# BatteryCharger.net
KiCad netlist of a schematic drawn in Altium Designer
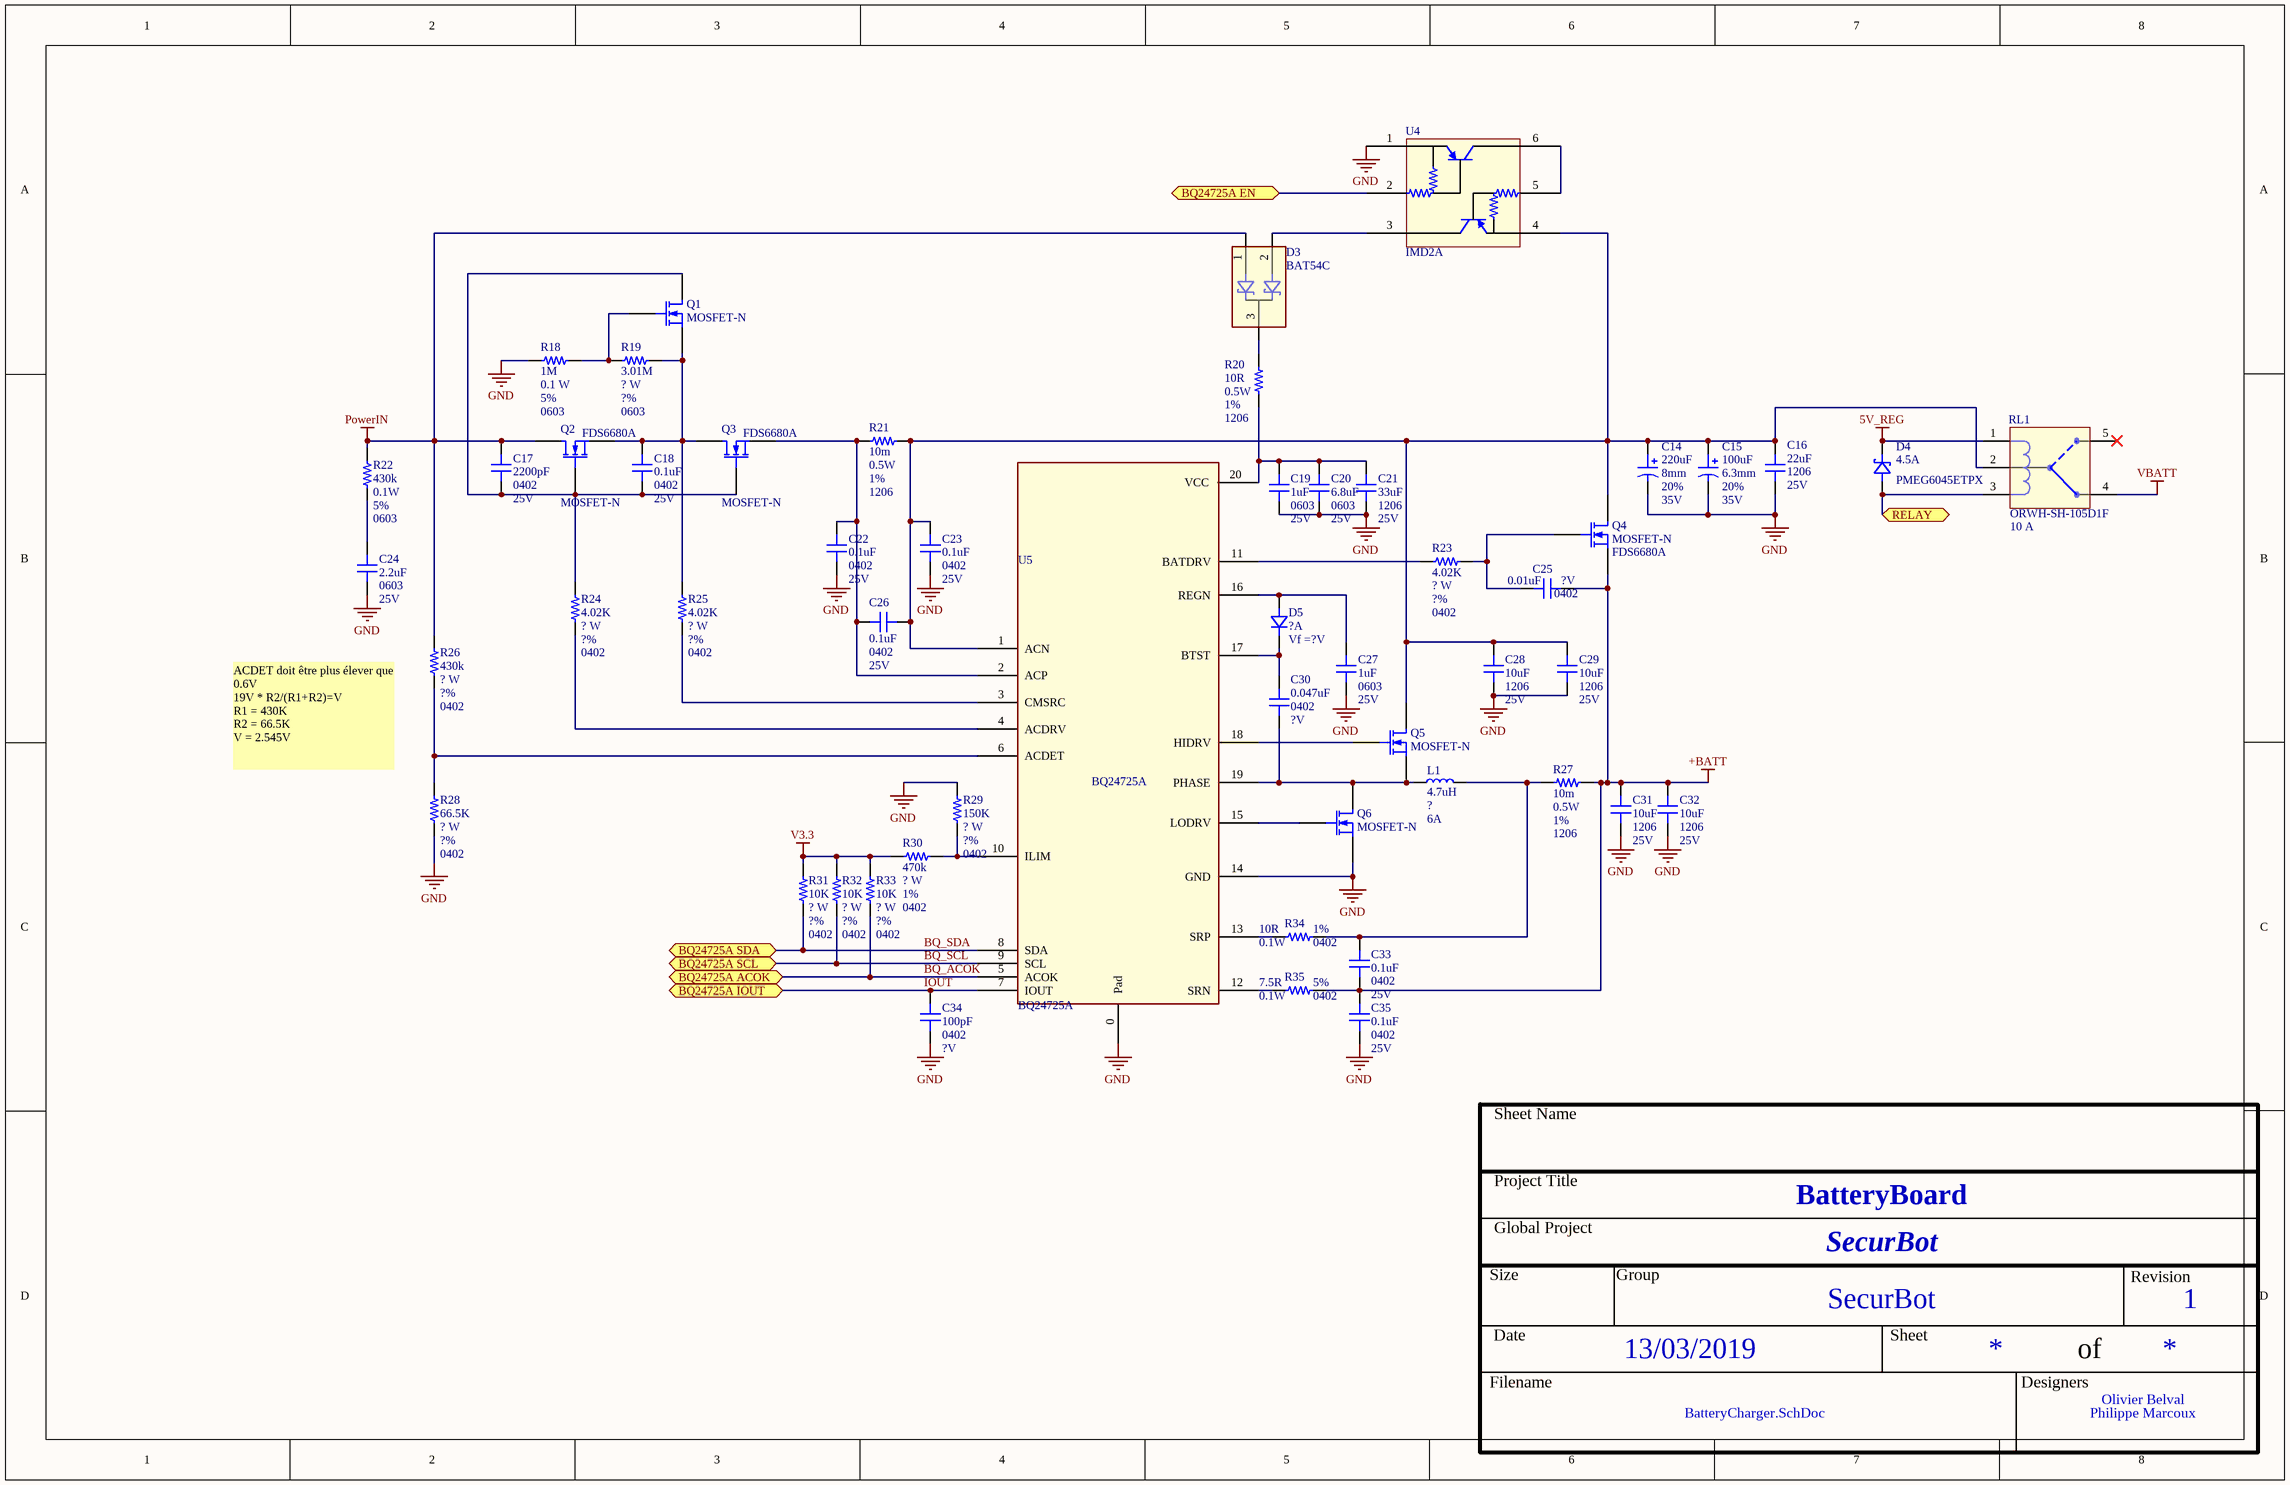
[diagram p0: BatteryCharger.SchDoc]

(export (version "E")
  (design (tool "Eeschema 10.0.6"))
  (components
    (comp (ref "C14")
      (value "220uF")
      (footprint "CAP UWT 8x10")
      (description "CAP ALU - 6.3mm")
      (fields
        (field (name "PACKAGE") "8mm")
        (field (name "TOLERANCE") "20%")
        (field (name "VOLTAGE") "35V")
        (field (name "PART NUMBER") "UWT1E221MNL1GS")
      )
      (libsource (lib "SecureBot") (part "CAP ALU - 6_3mm"))
    )
    (comp (ref "C15")
      (value "100uF")
      (footprint "CAP ALU - 6.3mm DIA")
      (description "CAP ALU - 6.3mm")
      (fields
        (field (name "PACKAGE") "6.3mm")
        (field (name "TOLERANCE") "20%")
        (field (name "VOLTAGE") "35V")
        (field (name "PART NUMBER") "UWT1E101MCL1GS")
      )
      (libsource (lib "SecureBot") (part "CAP ALU - 6_3mm"))
    )
    (comp (ref "C16")
      (value "22uF")
      (footprint "CAP_1206")
      (description "CAP - 1206")
      (fields
        (field (name "PART NUMBER") "CL31A226KAHNNNE")
        (field (name "PACKAGE") "1206")
        (field (name "VOLTAGE") "25V")
      )
      (libsource (lib "SecureBot") (part "CAP - 1206"))
    )
    (comp (ref "C17")
      (value "2200pF")
      (footprint "CAP_0402")
      (description "CAP - 0402")
      (fields
        (field (name "PART NUMBER") "AC0402KRX7R8BB222")
        (field (name "PACKAGE") "0402")
        (field (name "VOLTAGE") "25V")
      )
      (libsource (lib "SecureBot") (part "CAP - 0402"))
    )
    (comp (ref "C18")
      (value "0.1uF")
      (footprint "CAP_0402")
      (description "CAP - 0402")
      (fields
        (field (name "PART NUMBER") "CL05A104KA5NNNC")
        (field (name "PACKAGE") "0402")
        (field (name "VOLTAGE") "25V")
      )
      (libsource (lib "SecureBot") (part "CAP - 0402"))
    )
    (comp (ref "C19")
      (value "1uF")
      (footprint "CAP_0603")
      (description "CAP - 0603")
      (fields
        (field (name "PART NUMBER") "CL10A105KA8NNNC")
        (field (name "PACKAGE") "0603")
        (field (name "VOLTAGE") "25V")
      )
      (libsource (lib "SecureBot") (part "CAP - 0603"))
    )
    (comp (ref "C20")
      (value "6.8uF")
      (footprint "CAP_0603")
      (description "CAP - 0603")
      (fields
        (field (name "PART NUMBER") "C1608X5R1E685K080AC")
        (field (name "PACKAGE") "0603")
        (field (name "VOLTAGE") "25V")
      )
      (libsource (lib "SecureBot") (part "CAP - 0603"))
    )
    (comp (ref "C21")
      (value "33uF")
      (footprint "CAP_1206")
      (description "CAP - 1206")
      (fields
        (field (name "PART NUMBER") "C3216JB1E336M160AC")
        (field (name "PACKAGE") "1206")
        (field (name "VOLTAGE") "25V")
      )
      (libsource (lib "SecureBot") (part "CAP - 1206"))
    )
    (comp (ref "C22")
      (value "0.1uF")
      (footprint "CAP_0402")
      (description "CAP - 0402")
      (fields
        (field (name "PART NUMBER") "CL05A104KA5NNNC")
        (field (name "PACKAGE") "0402")
        (field (name "VOLTAGE") "25V")
      )
      (libsource (lib "SecureBot") (part "CAP - 0402"))
    )
    (comp (ref "C23")
      (value "0.1uF")
      (footprint "CAP_0402")
      (description "CAP - 0402")
      (fields
        (field (name "PART NUMBER") "CL05A104KA5NNNC")
        (field (name "PACKAGE") "0402")
        (field (name "VOLTAGE") "25V")
      )
      (libsource (lib "SecureBot") (part "CAP - 0402"))
    )
    (comp (ref "C24")
      (value "2.2uF")
      (footprint "CAP_0603")
      (description "CAP - 0603")
      (fields
        (field (name "PART NUMBER") "GRM188R61E225KA12D")
        (field (name "PACKAGE") "0603")
        (field (name "VOLTAGE") "25V")
      )
      (libsource (lib "SecureBot") (part "CAP - 0603"))
    )
    (comp (ref "C25")
      (value "0.01uF")
      (footprint "CAP_0402")
      (description "CAP - 0402")
      (fields
        (field (name "PART NUMBER") "CL05B103KA5NNNC")
        (field (name "PACKAGE") "0402")
        (field (name "VOLTAGE") "?V")
      )
      (libsource (lib "SecureBot") (part "CAP - 0402"))
    )
    (comp (ref "C26")
      (value "0.1uF")
      (footprint "CAP_0402")
      (description "CAP - 0402")
      (fields
        (field (name "PART NUMBER") "CL05A104KA5NNNC")
        (field (name "PACKAGE") "0402")
        (field (name "VOLTAGE") "25V")
      )
      (libsource (lib "SecureBot") (part "CAP - 0402"))
    )
    (comp (ref "C27")
      (value "1uF")
      (footprint "CAP_0603")
      (description "CAP - 0603")
      (fields
        (field (name "PART NUMBER") "CL10A105KA8NNNC")
        (field (name "PACKAGE") "0603")
        (field (name "VOLTAGE") "25V")
      )
      (libsource (lib "SecureBot") (part "CAP - 0603"))
    )
    (comp (ref "C28")
      (value "10uF")
      (footprint "CAP_1206")
      (description "CAP - 1206")
      (fields
        (field (name "PART NUMBER") "CL31A106KAHNFNE")
        (field (name "PACKAGE") "1206")
        (field (name "VOLTAGE") "25V")
      )
      (libsource (lib "SecureBot") (part "CAP - 1206"))
    )
    (comp (ref "C29")
      (value "10uF")
      (footprint "CAP_1206")
      (description "CAP - 1206")
      (fields
        (field (name "PART NUMBER") "CL31A106KAHNFNE")
        (field (name "PACKAGE") "1206")
        (field (name "VOLTAGE") "25V")
      )
      (libsource (lib "SecureBot") (part "CAP - 1206"))
    )
    (comp (ref "C30")
      (value "0.047uF")
      (footprint "CAP_0402")
      (description "CAP - 0402")
      (fields
        (field (name "PART NUMBER") "C0402C473K3RACAUTO")
        (field (name "PACKAGE") "0402")
        (field (name "VOLTAGE") "?V")
      )
      (libsource (lib "SecureBot") (part "CAP - 0402"))
    )
    (comp (ref "C31")
      (value "10uF")
      (footprint "CAP_1206")
      (description "CAP - 1206")
      (fields
        (field (name "PART NUMBER") "CL31A106KAHNFNE")
        (field (name "PACKAGE") "1206")
        (field (name "VOLTAGE") "25V")
      )
      (libsource (lib "SecureBot") (part "CAP - 1206"))
    )
    (comp (ref "C32")
      (value "10uF")
      (footprint "CAP_1206")
      (description "CAP - 1206")
      (fields
        (field (name "PART NUMBER") "CL31A106KAHNFNE")
        (field (name "PACKAGE") "1206")
        (field (name "VOLTAGE") "25V")
      )
      (libsource (lib "SecureBot") (part "CAP - 1206"))
    )
    (comp (ref "C33")
      (value "0.1uF")
      (footprint "CAP_0402")
      (description "CAP - 0402")
      (fields
        (field (name "PART NUMBER") "CL05A104KA5NNNC")
        (field (name "PACKAGE") "0402")
        (field (name "VOLTAGE") "25V")
      )
      (libsource (lib "SecureBot") (part "CAP - 0402"))
    )
    (comp (ref "C34")
      (value "100pF")
      (footprint "CAP_0402")
      (description "CAP - 0402")
      (fields
        (field (name "PART NUMBER") "CC0402KRX7R8BB101")
        (field (name "PACKAGE") "0402")
        (field (name "VOLTAGE") "?V")
      )
      (libsource (lib "SecureBot") (part "CAP - 0402"))
    )
    (comp (ref "C35")
      (value "0.1uF")
      (footprint "CAP_0402")
      (description "CAP - 0402")
      (fields
        (field (name "PART NUMBER") "CL05A104KA5NNNC")
        (field (name "PACKAGE") "0402")
        (field (name "VOLTAGE") "25V")
      )
      (libsource (lib "SecureBot") (part "CAP - 0402"))
    )
    (comp (ref "D3") (value "BAT54C") (footprint "BAT54C") (libsource (lib "SecureBot") (part "BAT54C")))
    (comp (ref "D4")
      (value "SCHOTTKEY")
      (footprint "DO-214AC_SOD128")
      (fields (field (name "CURRENT") "4.5A") (field (name "PART NUMBER") "PMEG6045ETPX"))
      (libsource (lib "SecureBot") (part "SCHOTTKEY"))
    )
    (comp (ref "D5")
      (value "DIODE BAT54")
      (footprint "BAT54")
      (fields
        (field (name "CURRENT") "?A")
        (field (name "VF") "Vf =?V")
        (field (name "PART NUMBER") "BAT54C")
      )
      (libsource (lib "SecureBot") (part "DIODE BAT54"))
    )
    (comp (ref "L1")
      (value "4.7uH")
      (footprint "ASPI-0630LR")
      (description "IND")
      (fields
        (field (name "PACKAGE") "?")
        (field (name "CURRENT") "6A")
        (field (name "PART NUMBER") "ASPI-0630LR-4R7M-T15")
      )
      (libsource (lib "SecureBot") (part "IND"))
    )
    (comp (ref "Q1")
      (value "MOSFET-N")
      (footprint "PG-SOT-323")
      (description "N-Channel MOSFET")
      (fields (field (name "PART NUMBER") "BSS138WH6327XTSA1") (field (name "PUBLISHER") "Altium Limited"))
      (libsource (lib "Miscellaneous Devices") (part "MOSFET-N"))
    )
    (comp (ref "Q2")
      (value "MOSFET-N")
      (footprint "SO-8 FDS6680AS")
      (description "N-Channel MOSFET")
      (fields (field (name "PART NUMBER") "FDS6680A") (field (name "PUBLISHER") "Altium Limited"))
      (libsource (lib "") (part "MOSFET-N_1"))
    )
    (comp (ref "Q3")
      (value "MOSFET-N")
      (footprint "SO-8 FDS6680AS")
      (description "N-Channel MOSFET")
      (fields (field (name "PART NUMBER") "FDS6680A") (field (name "PUBLISHER") "Altium Limited"))
      (libsource (lib "") (part "MOSFET-N_1"))
    )
    (comp (ref "Q4")
      (value "MOSFET-N")
      (footprint "SO-8 FDS6680AS")
      (description "N-Channel MOSFET")
      (fields (field (name "PART NUMBER") "FDS6680A") (field (name "PUBLISHER") "Altium Limited"))
      (libsource (lib "") (part "MOSFET-N_1"))
    )
    (comp (ref "Q5")
      (value "MOSFET-N")
      (footprint "SiS412DN")
      (description "N-Channel MOSFET")
      (fields (field (name "PART NUMBER") "SIS412DN-T1-GE3") (field (name "PUBLISHER") "Altium Limited"))
      (libsource (lib "") (part "MOSFET-N_1"))
    )
    (comp (ref "Q6")
      (value "MOSFET-N")
      (footprint "SiS412DN")
      (description "N-Channel MOSFET")
      (fields (field (name "PART NUMBER") "SIS412DN-T1-GE3") (field (name "PUBLISHER") "Altium Limited"))
      (libsource (lib "") (part "MOSFET-N_1"))
    )
    (comp (ref "R18")
      (value "1M")
      (footprint "RES_0603")
      (description "RES - 0603")
      (fields
        (field (name "PART NUMBER") "CRGCQ0603J1M0")
        (field (name "WATT") "0.1 W")
        (field (name "TOLERANCE") "5%")
        (field (name "PACKAGE") "0603")
      )
      (libsource (lib "SecureBot") (part "RES - 0603"))
    )
    (comp (ref "R19")
      (value "3.01M")
      (footprint "RES_0603")
      (description "RES - 0603")
      (fields
        (field (name "PART NUMBER") "RC0603FR-073M01L")
        (field (name "WATT") "? W")
        (field (name "TOLERANCE") "?%")
        (field (name "PACKAGE") "0603")
      )
      (libsource (lib "SecureBot") (part "RES - 0603"))
    )
    (comp (ref "R20")
      (value "10R")
      (footprint "RES_1206")
      (description "RES - 1206")
      (fields
        (field (name "PART NUMBER") "CRM1206-FX-10R0ELF")
        (field (name "WATT") "0.5W")
        (field (name "TOLERANCE") "1%")
        (field (name "PACKAGE") "1206")
      )
      (libsource (lib "SecureBot") (part "RES - 1206"))
    )
    (comp (ref "R21")
      (value "10m")
      (footprint "RES_1206")
      (description "RES - 1206")
      (fields
        (field (name "PART NUMBER") "KRL1632E-M-R010-F-T5")
        (field (name "WATT") "0.5W")
        (field (name "TOLERANCE") "1%")
        (field (name "PACKAGE") "1206")
      )
      (libsource (lib "SecureBot") (part "RES - 1206"))
    )
    (comp (ref "R22")
      (value "430k")
      (footprint "RES_0603")
      (description "RES - 0603")
      (fields
        (field (name "PART NUMBER") "RC0603JR-07430KL")
        (field (name "WATT") "0.1W")
        (field (name "TOLERANCE") "5%")
        (field (name "PACKAGE") "0603")
      )
      (libsource (lib "SecureBot") (part "RES - 0603"))
    )
    (comp (ref "R23")
      (value "4.02K")
      (footprint "RES_0402")
      (description "RES - 0402")
      (fields
        (field (name "PART NUMBER") "ERJ-2RKF4021X")
        (field (name "WATT") "? W")
        (field (name "TOLERANCE") "?%")
        (field (name "PACKAGE") "0402")
      )
      (libsource (lib "SecureBot") (part "RES - 0402"))
    )
    (comp (ref "R24")
      (value "4.02K")
      (footprint "RES_0402")
      (description "RES - 0402")
      (fields
        (field (name "PART NUMBER") "ERJ-2RKF4021X")
        (field (name "WATT") "? W")
        (field (name "TOLERANCE") "?%")
        (field (name "PACKAGE") "0402")
      )
      (libsource (lib "SecureBot") (part "RES - 0402"))
    )
    (comp (ref "R25")
      (value "4.02K")
      (footprint "RES_0402")
      (description "RES - 0402")
      (fields
        (field (name "PART NUMBER") "ERJ-2RKF4021X")
        (field (name "WATT") "? W")
        (field (name "TOLERANCE") "?%")
        (field (name "PACKAGE") "0402")
      )
      (libsource (lib "SecureBot") (part "RES - 0402"))
    )
    (comp (ref "R26")
      (value "430k")
      (footprint "RES_0402")
      (description "RES - 0402")
      (fields
        (field (name "PART NUMBER") "RC0402FR-07430KL")
        (field (name "WATT") "? W")
        (field (name "TOLERANCE") "?%")
        (field (name "PACKAGE") "0402")
      )
      (libsource (lib "SecureBot") (part "RES - 0402"))
    )
    (comp (ref "R27")
      (value "10m")
      (footprint "RES_1206")
      (description "RES - 1206")
      (fields
        (field (name "PART NUMBER") "KRL1632E-M-R010-F-T5")
        (field (name "WATT") "0.5W")
        (field (name "TOLERANCE") "1%")
        (field (name "PACKAGE") "1206")
      )
      (libsource (lib "SecureBot") (part "RES - 1206"))
    )
    (comp (ref "R28")
      (value "66.5K")
      (footprint "RES_0402")
      (description "RES - 0402")
      (fields
        (field (name "PART NUMBER") "RMCF0402FT66K5")
        (field (name "WATT") "? W")
        (field (name "TOLERANCE") "?%")
        (field (name "PACKAGE") "0402")
      )
      (libsource (lib "SecureBot") (part "RES - 0402"))
    )
    (comp (ref "R29")
      (value "150K")
      (footprint "RES_0402")
      (description "RES - 0402")
      (fields
        (field (name "PART NUMBER") "MCS04020C1503FE000")
        (field (name "WATT") "? W")
        (field (name "TOLERANCE") "?%")
        (field (name "PACKAGE") "0402")
      )
      (libsource (lib "SecureBot") (part "RES - 0402"))
    )
    (comp (ref "R30")
      (value "470k")
      (footprint "RES_0402")
      (description "RES - 0402")
      (fields
        (field (name "PART NUMBER") "MCS04020C4703FE000")
        (field (name "WATT") "? W")
        (field (name "TOLERANCE") "1%")
        (field (name "PACKAGE") "0402")
      )
      (libsource (lib "SecureBot") (part "RES - 0402"))
    )
    (comp (ref "R31")
      (value "10K")
      (footprint "RES_0402")
      (description "RES - 0402")
      (fields
        (field (name "PART NUMBER") "MCS0402MC1002FE000")
        (field (name "WATT") "? W")
        (field (name "TOLERANCE") "?%")
        (field (name "PACKAGE") "0402")
      )
      (libsource (lib "SecureBot") (part "RES - 0402"))
    )
    (comp (ref "R32")
      (value "10K")
      (footprint "RES_0402")
      (description "RES - 0402")
      (fields
        (field (name "PART NUMBER") "MCS0402MC1002FE000")
        (field (name "WATT") "? W")
        (field (name "TOLERANCE") "?%")
        (field (name "PACKAGE") "0402")
      )
      (libsource (lib "SecureBot") (part "RES - 0402"))
    )
    (comp (ref "R33")
      (value "10K")
      (footprint "RES_0402")
      (description "RES - 0402")
      (fields
        (field (name "PART NUMBER") "MCS0402MC1002FE000")
        (field (name "WATT") "? W")
        (field (name "TOLERANCE") "?%")
        (field (name "PACKAGE") "0402")
      )
      (libsource (lib "SecureBot") (part "RES - 0402"))
    )
    (comp (ref "R34")
      (value "10R")
      (footprint "RES_0402")
      (description "RES - 0402")
      (fields
        (field (name "PART NUMBER") "ERJ-2RKF10R0X")
        (field (name "WATT") "0.1W")
        (field (name "TOLERANCE") "1%")
        (field (name "PACKAGE") "0402")
      )
      (libsource (lib "SecureBot") (part "RES - 0402"))
    )
    (comp (ref "R35")
      (value "7.5R")
      (footprint "RES_0402")
      (description "RES - 0402")
      (fields
        (field (name "PART NUMBER") "ERJ-2GEJ7R5X")
        (field (name "WATT") "0.1W")
        (field (name "TOLERANCE") "5%")
        (field (name "PACKAGE") "0402")
      )
      (libsource (lib "SecureBot") (part "RES - 0402"))
    )
    (comp (ref "RL1")
      (value "Relay SPDT")
      (footprint "ORWH-SH")
      (fields (field (name "PART NUMBER") "ORWH-SH-105D1F") (field (name "A MAX") "10 A"))
      (libsource (lib "SecureBot") (part "Relay SPDT"))
    )
    (comp (ref "U4")
      (value "IMD2A")
      (footprint "IMD2A")
      (description "Dual digital Transistor")
      (libsource (lib "SecureBot") (part "IMD2A"))
    )
    (comp (ref "U5")
      (value "BQ24725A")
      (footprint "bq24725A")
      (libsource (lib "SecureBot") (part "BQ24725A"))
    )
  )
  (nets
    (net (code "1") (name "+BATT") (class "Default")
      (node (ref "C25") (pin "2") (pinfunction "2_2") (pintype "passive"))
      (node (ref "C31") (pin "1") (pinfunction "1_1") (pintype "passive"))
      (node (ref "C32") (pin "1") (pinfunction "1_1") (pintype "passive"))
      (node (ref "C33") (pin "1") (pinfunction "1_1") (pintype "passive"))
      (node (ref "C35") (pin "2") (pinfunction "2_2") (pintype "passive"))
      (node (ref "Q4") (pin "3") (pinfunction "S_3") (pintype "passive"))
      (node (ref "R27") (pin "2") (pinfunction "2_2") (pintype "passive"))
      (node (ref "R35") (pin "2") (pinfunction "2_2") (pintype "passive"))
    )
    (net (code "2") (name "/BQ24725A EN") (class "Default")
      (node (ref "U4") (pin "2") (pinfunction "2_2") (pintype "passive"))
    )
    (net (code "3") (name "/BQ_ACOK") (class "Default")
      (node (ref "R33") (pin "2") (pinfunction "2_2") (pintype "passive"))
      (node (ref "U5") (pin "5") (pinfunction "ACOK_5") (pintype "passive"))
    )
    (net (code "4") (name "/BQ_SCL") (class "Default")
      (node (ref "R32") (pin "2") (pinfunction "2_2") (pintype "passive"))
      (node (ref "U5") (pin "9") (pinfunction "SCL_9") (pintype "passive"))
    )
    (net (code "5") (name "/BQ_SDA") (class "Default")
      (node (ref "R31") (pin "2") (pinfunction "2_2") (pintype "passive"))
      (node (ref "U5") (pin "8") (pinfunction "SDA_8") (pintype "passive"))
    )
    (net (code "6") (name "/IOUT") (class "Default")
      (node (ref "C34") (pin "1") (pinfunction "1_1") (pintype "passive"))
      (node (ref "U5") (pin "7") (pinfunction "IOUT_7") (pintype "passive"))
    )
    (net (code "7") (name "/RELAY") (class "Default")
      (node (ref "D4") (pin "1") (pinfunction "1_1") (pintype "passive"))
      (node (ref "RL1") (pin "3") (pinfunction "3_3") (pintype "passive"))
    )
    (net (code "8") (name "5V_REG") (class "Default")
      (node (ref "D4") (pin "2") (pinfunction "2_2") (pintype "passive"))
      (node (ref "RL1") (pin "1") (pinfunction "1_1") (pintype "passive"))
    )
    (net (code "9") (name "GND") (class "Default")
      (node (ref "C14") (pin "2") (pinfunction "2_2") (pintype "passive"))
      (node (ref "C15") (pin "2") (pinfunction "2_2") (pintype "passive"))
      (node (ref "C16") (pin "2") (pinfunction "2_2") (pintype "passive"))
      (node (ref "C19") (pin "2") (pinfunction "2_2") (pintype "passive"))
      (node (ref "C20") (pin "2") (pinfunction "2_2") (pintype "passive"))
      (node (ref "C21") (pin "2") (pinfunction "2_2") (pintype "passive"))
      (node (ref "C22") (pin "1") (pinfunction "1_1") (pintype "passive"))
      (node (ref "C23") (pin "1") (pinfunction "1_1") (pintype "passive"))
      (node (ref "C24") (pin "2") (pinfunction "2_2") (pintype "passive"))
      (node (ref "C27") (pin "2") (pinfunction "2_2") (pintype "passive"))
      (node (ref "C28") (pin "2") (pinfunction "2_2") (pintype "passive"))
      (node (ref "C29") (pin "2") (pinfunction "2_2") (pintype "passive"))
      (node (ref "C31") (pin "2") (pinfunction "2_2") (pintype "passive"))
      (node (ref "C32") (pin "2") (pinfunction "2_2") (pintype "passive"))
      (node (ref "C34") (pin "2") (pinfunction "2_2") (pintype "passive"))
      (node (ref "C35") (pin "1") (pinfunction "1_1") (pintype "passive"))
      (node (ref "Q6") (pin "3") (pinfunction "S_3") (pintype "passive"))
      (node (ref "R18") (pin "1") (pinfunction "1_1") (pintype "passive"))
      (node (ref "R28") (pin "2") (pinfunction "2_2") (pintype "passive"))
      (node (ref "R29") (pin "2") (pinfunction "2_2") (pintype "passive"))
      (node (ref "U4") (pin "1") (pinfunction "1_1") (pintype "passive"))
      (node (ref "U5") (pin "0") (pinfunction "Pad_0") (pintype "passive"))
      (node (ref "U5") (pin "14") (pinfunction "GND_14") (pintype "passive"))
    )
    (net (code "10") (name "Net-(C24-Pad1)") (class "Default")
      (node (ref "C24") (pin "1") (pinfunction "1_1") (pintype "passive"))
      (node (ref "R22") (pin "2") (pinfunction "2_2") (pintype "passive"))
    )
    (net (code "11") (name "Net-(C33-Pad2)") (class "Default")
      (node (ref "C33") (pin "2") (pinfunction "2_2") (pintype "passive"))
      (node (ref "L1") (pin "2") (pinfunction "2_2") (pintype "passive"))
      (node (ref "R27") (pin "1") (pinfunction "1_1") (pintype "passive"))
      (node (ref "R34") (pin "2") (pinfunction "2_2") (pintype "passive"))
    )
    (net (code "12") (name "Net-(D3-Pad2)") (class "Default")
      (node (ref "D3") (pin "2") (pinfunction "2_2") (pintype "passive"))
      (node (ref "U4") (pin "3") (pinfunction "3_3") (pintype "passive"))
    )
    (net (code "13") (name "Net-(D3-Pad3)") (class "Default")
      (node (ref "D3") (pin "3") (pinfunction "3_3") (pintype "passive"))
      (node (ref "R20") (pin "2") (pinfunction "2_2") (pintype "passive"))
    )
    (net (code "14") (name "Net-(Q1-D)") (class "Default")
      (node (ref "C17") (pin "1") (pinfunction "1_1") (pintype "passive"))
      (node (ref "C18") (pin "1") (pinfunction "1_1") (pintype "passive"))
      (node (ref "Q1") (pin "3") (pinfunction "D_3") (pintype "passive"))
      (node (ref "Q2") (pin "2") (pinfunction "G_2") (pintype "passive"))
      (node (ref "Q3") (pin "2") (pinfunction "G_2") (pintype "passive"))
      (node (ref "R24") (pin "1") (pinfunction "1_1") (pintype "passive"))
    )
    (net (code "15") (name "Net-(Q1-G)") (class "Default")
      (node (ref "Q1") (pin "1") (pinfunction "G_1") (pintype "passive"))
      (node (ref "R18") (pin "2") (pinfunction "2_2") (pintype "passive"))
      (node (ref "R19") (pin "1") (pinfunction "1_1") (pintype "passive"))
    )
    (net (code "16") (name "Net-(Q1-S)") (class "Default")
      (node (ref "C18") (pin "2") (pinfunction "2_2") (pintype "passive"))
      (node (ref "Q1") (pin "2") (pinfunction "S_2") (pintype "passive"))
      (node (ref "Q2") (pin "3") (pinfunction "S_3") (pintype "passive"))
      (node (ref "Q3") (pin "1") (pinfunction "D_1") (pintype "passive"))
      (node (ref "R19") (pin "2") (pinfunction "2_2") (pintype "passive"))
      (node (ref "R25") (pin "1") (pinfunction "1_1") (pintype "passive"))
    )
    (net (code "17") (name "Net-(Q3-S)") (class "Default")
      (node (ref "C22") (pin "2") (pinfunction "2_2") (pintype "passive"))
      (node (ref "C26") (pin "2") (pinfunction "2_2") (pintype "passive"))
      (node (ref "Q3") (pin "3") (pinfunction "S_3") (pintype "passive"))
      (node (ref "R21") (pin "1") (pinfunction "1_1") (pintype "passive"))
      (node (ref "U5") (pin "2") (pinfunction "ACP_2") (pintype "passive"))
    )
    (net (code "18") (name "Net-(Q4-D)") (class "Default")
      (node (ref "C14") (pin "1") (pinfunction "1_1") (pintype "passive"))
      (node (ref "C15") (pin "1") (pinfunction "1_1") (pintype "passive"))
      (node (ref "C16") (pin "1") (pinfunction "1_1") (pintype "passive"))
      (node (ref "C23") (pin "2") (pinfunction "2_2") (pintype "passive"))
      (node (ref "C26") (pin "1") (pinfunction "1_1") (pintype "passive"))
      (node (ref "C28") (pin "1") (pinfunction "1_1") (pintype "passive"))
      (node (ref "C29") (pin "1") (pinfunction "1_1") (pintype "passive"))
      (node (ref "Q4") (pin "1") (pinfunction "D_1") (pintype "passive"))
      (node (ref "Q5") (pin "1") (pinfunction "D_1") (pintype "passive"))
      (node (ref "R21") (pin "2") (pinfunction "2_2") (pintype "passive"))
      (node (ref "RL1") (pin "2") (pinfunction "2_2") (pintype "passive"))
      (node (ref "U4") (pin "4") (pinfunction "4_4") (pintype "passive"))
      (node (ref "U5") (pin "1") (pinfunction "ACN_1") (pintype "passive"))
    )
    (net (code "19") (name "Net-(Q4-G)") (class "Default")
      (node (ref "C25") (pin "1") (pinfunction "1_1") (pintype "passive"))
      (node (ref "Q4") (pin "2") (pinfunction "G_2") (pintype "passive"))
      (node (ref "R23") (pin "2") (pinfunction "2_2") (pintype "passive"))
    )
    (net (code "20") (name "Net-(Q5-G)") (class "Default")
      (node (ref "Q5") (pin "2") (pinfunction "G_2") (pintype "passive"))
      (node (ref "U5") (pin "18") (pinfunction "HIDRV_18") (pintype "passive"))
    )
    (net (code "21") (name "Net-(Q5-S)") (class "Default")
      (node (ref "C30") (pin "2") (pinfunction "2_2") (pintype "passive"))
      (node (ref "L1") (pin "1") (pinfunction "1_1") (pintype "passive"))
      (node (ref "Q5") (pin "3") (pinfunction "S_3") (pintype "passive"))
      (node (ref "Q6") (pin "1") (pinfunction "D_1") (pintype "passive"))
      (node (ref "U5") (pin "19") (pinfunction "PHASE_19") (pintype "passive"))
    )
    (net (code "22") (name "Net-(Q6-G)") (class "Default")
      (node (ref "Q6") (pin "2") (pinfunction "G_2") (pintype "passive"))
      (node (ref "U5") (pin "15") (pinfunction "LODRV_15") (pintype "passive"))
    )
    (net (code "23") (name "Net-(U4-Pad5)") (class "Default")
      (node (ref "U4") (pin "5") (pinfunction "5_5") (pintype "passive"))
      (node (ref "U4") (pin "6") (pinfunction "6_6") (pintype "passive"))
    )
    (net (code "24") (name "Net-(U5-ACDET)") (class "Default")
      (node (ref "R26") (pin "2") (pinfunction "2_2") (pintype "passive"))
      (node (ref "R28") (pin "1") (pinfunction "1_1") (pintype "passive"))
      (node (ref "U5") (pin "6") (pinfunction "ACDET_6") (pintype "passive"))
    )
    (net (code "25") (name "Net-(U5-ACDRV)") (class "Default")
      (node (ref "R24") (pin "2") (pinfunction "2_2") (pintype "passive"))
      (node (ref "U5") (pin "4") (pinfunction "ACDRV_4") (pintype "passive"))
    )
    (net (code "26") (name "Net-(U5-BATDRV)") (class "Default")
      (node (ref "R23") (pin "1") (pinfunction "1_1") (pintype "passive"))
      (node (ref "U5") (pin "11") (pinfunction "BATDRV_11") (pintype "passive"))
    )
    (net (code "27") (name "Net-(U5-BTST)") (class "Default")
      (node (ref "C30") (pin "1") (pinfunction "1_1") (pintype "passive"))
      (node (ref "D5") (pin "3") (pinfunction "3_3") (pintype "passive"))
      (node (ref "U5") (pin "17") (pinfunction "BTST_17") (pintype "passive"))
    )
    (net (code "28") (name "Net-(U5-CMSRC)") (class "Default")
      (node (ref "R25") (pin "2") (pinfunction "2_2") (pintype "passive"))
      (node (ref "U5") (pin "3") (pinfunction "CMSRC_3") (pintype "passive"))
    )
    (net (code "29") (name "Net-(U5-ILIM)") (class "Default")
      (node (ref "R29") (pin "1") (pinfunction "1_1") (pintype "passive"))
      (node (ref "R30") (pin "1") (pinfunction "1_1") (pintype "passive"))
      (node (ref "U5") (pin "10") (pinfunction "ILIM_10") (pintype "passive"))
    )
    (net (code "30") (name "Net-(U5-REGN)") (class "Default")
      (node (ref "C27") (pin "1") (pinfunction "1_1") (pintype "passive"))
      (node (ref "D5") (pin "1") (pinfunction "1_1") (pintype "passive"))
      (node (ref "U5") (pin "16") (pinfunction "REGN_16") (pintype "passive"))
    )
    (net (code "31") (name "Net-(U5-SRN)") (class "Default")
      (node (ref "R35") (pin "1") (pinfunction "1_1") (pintype "passive"))
      (node (ref "U5") (pin "12") (pinfunction "SRN_12") (pintype "passive"))
    )
    (net (code "32") (name "Net-(U5-SRP)") (class "Default")
      (node (ref "R34") (pin "1") (pinfunction "1_1") (pintype "passive"))
      (node (ref "U5") (pin "13") (pinfunction "SRP_13") (pintype "passive"))
    )
    (net (code "33") (name "Net-(U5-VCC)") (class "Default")
      (node (ref "C19") (pin "1") (pinfunction "1_1") (pintype "passive"))
      (node (ref "C20") (pin "1") (pinfunction "1_1") (pintype "passive"))
      (node (ref "C21") (pin "1") (pinfunction "1_1") (pintype "passive"))
      (node (ref "R20") (pin "1") (pinfunction "1_1") (pintype "passive"))
      (node (ref "U5") (pin "20") (pinfunction "VCC_20") (pintype "passive"))
    )
    (net (code "34") (name "PowerIN") (class "Default")
      (node (ref "C17") (pin "2") (pinfunction "2_2") (pintype "passive"))
      (node (ref "D3") (pin "1") (pinfunction "1_1") (pintype "passive"))
      (node (ref "Q2") (pin "1") (pinfunction "D_1") (pintype "passive"))
      (node (ref "R22") (pin "1") (pinfunction "1_1") (pintype "passive"))
      (node (ref "R26") (pin "1") (pinfunction "1_1") (pintype "passive"))
    )
    (net (code "35") (name "V3.3") (class "Default")
      (node (ref "R30") (pin "2") (pinfunction "2_2") (pintype "passive"))
      (node (ref "R31") (pin "1") (pinfunction "1_1") (pintype "passive"))
      (node (ref "R32") (pin "1") (pinfunction "1_1") (pintype "passive"))
      (node (ref "R33") (pin "1") (pinfunction "1_1") (pintype "passive"))
    )
    (net (code "36") (name "VBATT") (class "Default")
      (node (ref "RL1") (pin "4") (pinfunction "4_4") (pintype "passive"))
    )
    (net (code "37") (name "unconnected-(RL1-Pad5)") (class "Default")
      (node (ref "RL1") (pin "5") (pinfunction "5_5") (pintype "passive+no_connect"))
    )
  )
)
